# 12VDC.net
KiCad netlist of a schematic drawn in Altium Designer
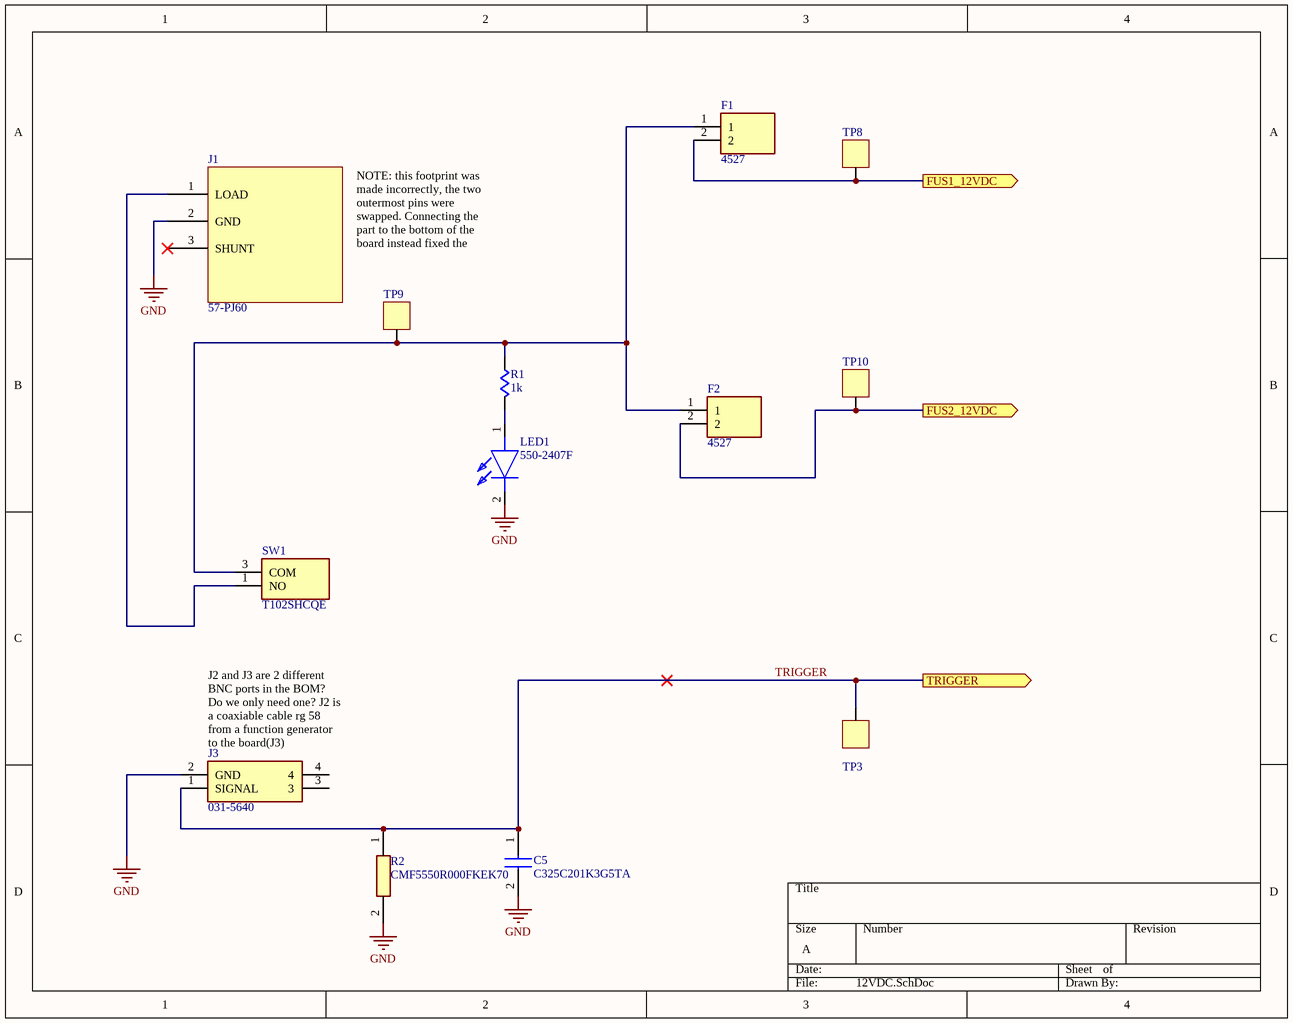
[diagram p0: 12VDC.SchDoc]

(export (version "E")
  (design (tool "Eeschema 10.0.6"))
  (components
    (comp (ref "C5")
      (value "C325C201K3G5TA")
      (footprint "C325C201K3G5TA")
      (description "Capacitor 200 pF")
      (libsource (lib "pulser_driver_symbols") (part "C325C201K3G5TA"))
    )
    (comp (ref "F1")
      (value "4527")
      (footprint "4527")
      (description "Undefined or Miscellaneous")
      (fields (field (name "MOUSER2 PART NUMBER") "534-4527"))
      (libsource (lib "pulser_driver_symbols") (part "4527"))
    )
    (comp (ref "F2")
      (value "4527")
      (footprint "4527")
      (description "Undefined or Miscellaneous")
      (fields (field (name "MOUSER2 PART NUMBER") "534-4527"))
      (libsource (lib "pulser_driver_symbols") (part "4527"))
    )
    (comp (ref "J1")
      (value "57-PJ60")
      (footprint "57-PJ60")
      (libsource (lib "pulser_driver_symbols") (part "57-PJ60"))
    )
    (comp (ref "J3")
      (value "031-5640")
      (footprint "031-5640")
      (description "Connector")
      (fields (field (name "MANUFACTURER_PART_NUMBER") "031-5640-1010"))
      (libsource (lib "pulser_driver_symbols") (part "031-5640"))
    )
    (comp (ref "LED1")
      (value "550-2407F")
      (footprint "5502407F")
      (description "LED")
      (fields (field (name "MOUSER2 PART NUMBER") "645-550-2407F"))
      (libsource (lib "pulser_driver_symbols") (part "550-2407F"))
    )
    (comp (ref "R1")
      (value "1k")
      (footprint "CMF551K0000FKR6")
      (description "Metal Film Resistors - Through Hole 1/2W 1Kohms 1%")
      (libsource (lib "pulser_driver_symbols") (part "CMF551K0000FKR6"))
    )
    (comp (ref "R2")
      (value "CMF5550R000FKEK70")
      (footprint "RESAD1526W69L610D229")
      (description "Resistor 50ohm")
      (libsource (lib "pulser_driver_symbols") (part "CMF5550R000FKEK70"))
    )
    (comp (ref "SW1")
      (value "T102SHCQE")
      (footprint "T102SHCQE")
      (description "Switch")
      (libsource (lib "pulser_driver_symbols") (part "T102SHCQE"))
    )
    (comp (ref "TP3")
      (value "5261")
      (footprint "5261")
      (description "TEST POINT grabber (BLACK) - MINIATURE")
      (libsource (lib "") (part "5261_1"))
    )
    (comp (ref "TP8")
      (value "5261")
      (footprint "5261")
      (description "TEST POINT grabber (BLACK) - MINIATURE")
      (libsource (lib "pulser_driver_symbols") (part "5261"))
    )
    (comp (ref "TP9")
      (value "5261")
      (footprint "5261")
      (description "TEST POINT grabber (BLACK) - MINIATURE")
      (libsource (lib "pulser_driver_symbols") (part "5261"))
    )
    (comp (ref "TP10")
      (value "5261")
      (footprint "5261")
      (description "TEST POINT grabber (BLACK) - MINIATURE")
      (libsource (lib "pulser_driver_symbols") (part "5261"))
    )
  )
  (nets
    (net (code "1") (name "/FUS1_12VDC") (class "Default")
      (node (ref "F1") (pin "2") (pinfunction "2_2") (pintype "passive"))
      (node (ref "TP8") (pin "1") (pinfunction "1_1") (pintype "passive"))
    )
    (net (code "2") (name "/FUS2_12VDC") (class "Default")
      (node (ref "F2") (pin "2") (pinfunction "2_2") (pintype "passive"))
      (node (ref "TP10") (pin "1") (pinfunction "1_1") (pintype "passive"))
    )
    (net (code "3") (name "/TRIGGER") (class "Default")
      (node (ref "C5") (pin "1") (pinfunction "1_1") (pintype "passive"))
      (node (ref "J3") (pin "1") (pinfunction "SIGNAL_1") (pintype "passive"))
      (node (ref "R2") (pin "1") (pinfunction "1_1") (pintype "passive"))
      (node (ref "TP3") (pin "1") (pinfunction "1_1") (pintype "passive"))
    )
    (net (code "4") (name "GND") (class "Default")
      (node (ref "C5") (pin "2") (pinfunction "2_2") (pintype "passive"))
      (node (ref "J1") (pin "2") (pinfunction "GND_2") (pintype "passive"))
      (node (ref "J3") (pin "2") (pinfunction "GND_2") (pintype "passive"))
      (node (ref "LED1") (pin "2") (pinfunction "K_2") (pintype "passive"))
      (node (ref "R2") (pin "2") (pinfunction "2_2") (pintype "passive"))
    )
    (net (code "5") (name "Net-(J1-LOAD)") (class "Default")
      (node (ref "J1") (pin "1") (pinfunction "LOAD_1") (pintype "passive"))
      (node (ref "SW1") (pin "1") (pinfunction "NO_1") (pintype "passive"))
    )
    (net (code "6") (name "Net-(LED1-A)") (class "Default")
      (node (ref "LED1") (pin "1") (pinfunction "A_1") (pintype "passive"))
      (node (ref "R1") (pin "2") (pinfunction "2_2") (pintype "passive"))
    )
    (net (code "7") (name "Net-(SW1-COM)") (class "Default")
      (node (ref "F1") (pin "1") (pinfunction "1_1") (pintype "passive"))
      (node (ref "F2") (pin "1") (pinfunction "1_1") (pintype "passive"))
      (node (ref "R1") (pin "1") (pinfunction "1_1") (pintype "passive"))
      (node (ref "SW1") (pin "3") (pinfunction "COM_3") (pintype "passive"))
      (node (ref "TP9") (pin "1") (pinfunction "1_1") (pintype "passive"))
    )
    (net (code "8") (name "unconnected-(J1-SHUNT-Pad3)") (class "Default")
      (node (ref "J1") (pin "3") (pinfunction "SHUNT_3") (pintype "passive+no_connect"))
    )
    (net (code "9") (name "unconnected-(J3-Pad3)") (class "Default")
      (node (ref "J3") (pin "3") (pinfunction "3_3") (pintype "passive"))
    )
    (net (code "10") (name "unconnected-(J3-Pad4)") (class "Default")
      (node (ref "J3") (pin "4") (pinfunction "4_4") (pintype "passive"))
    )
  )
)
